# OBDShield_1_1.net
KiCad netlist of a schematic drawn in EAGLE
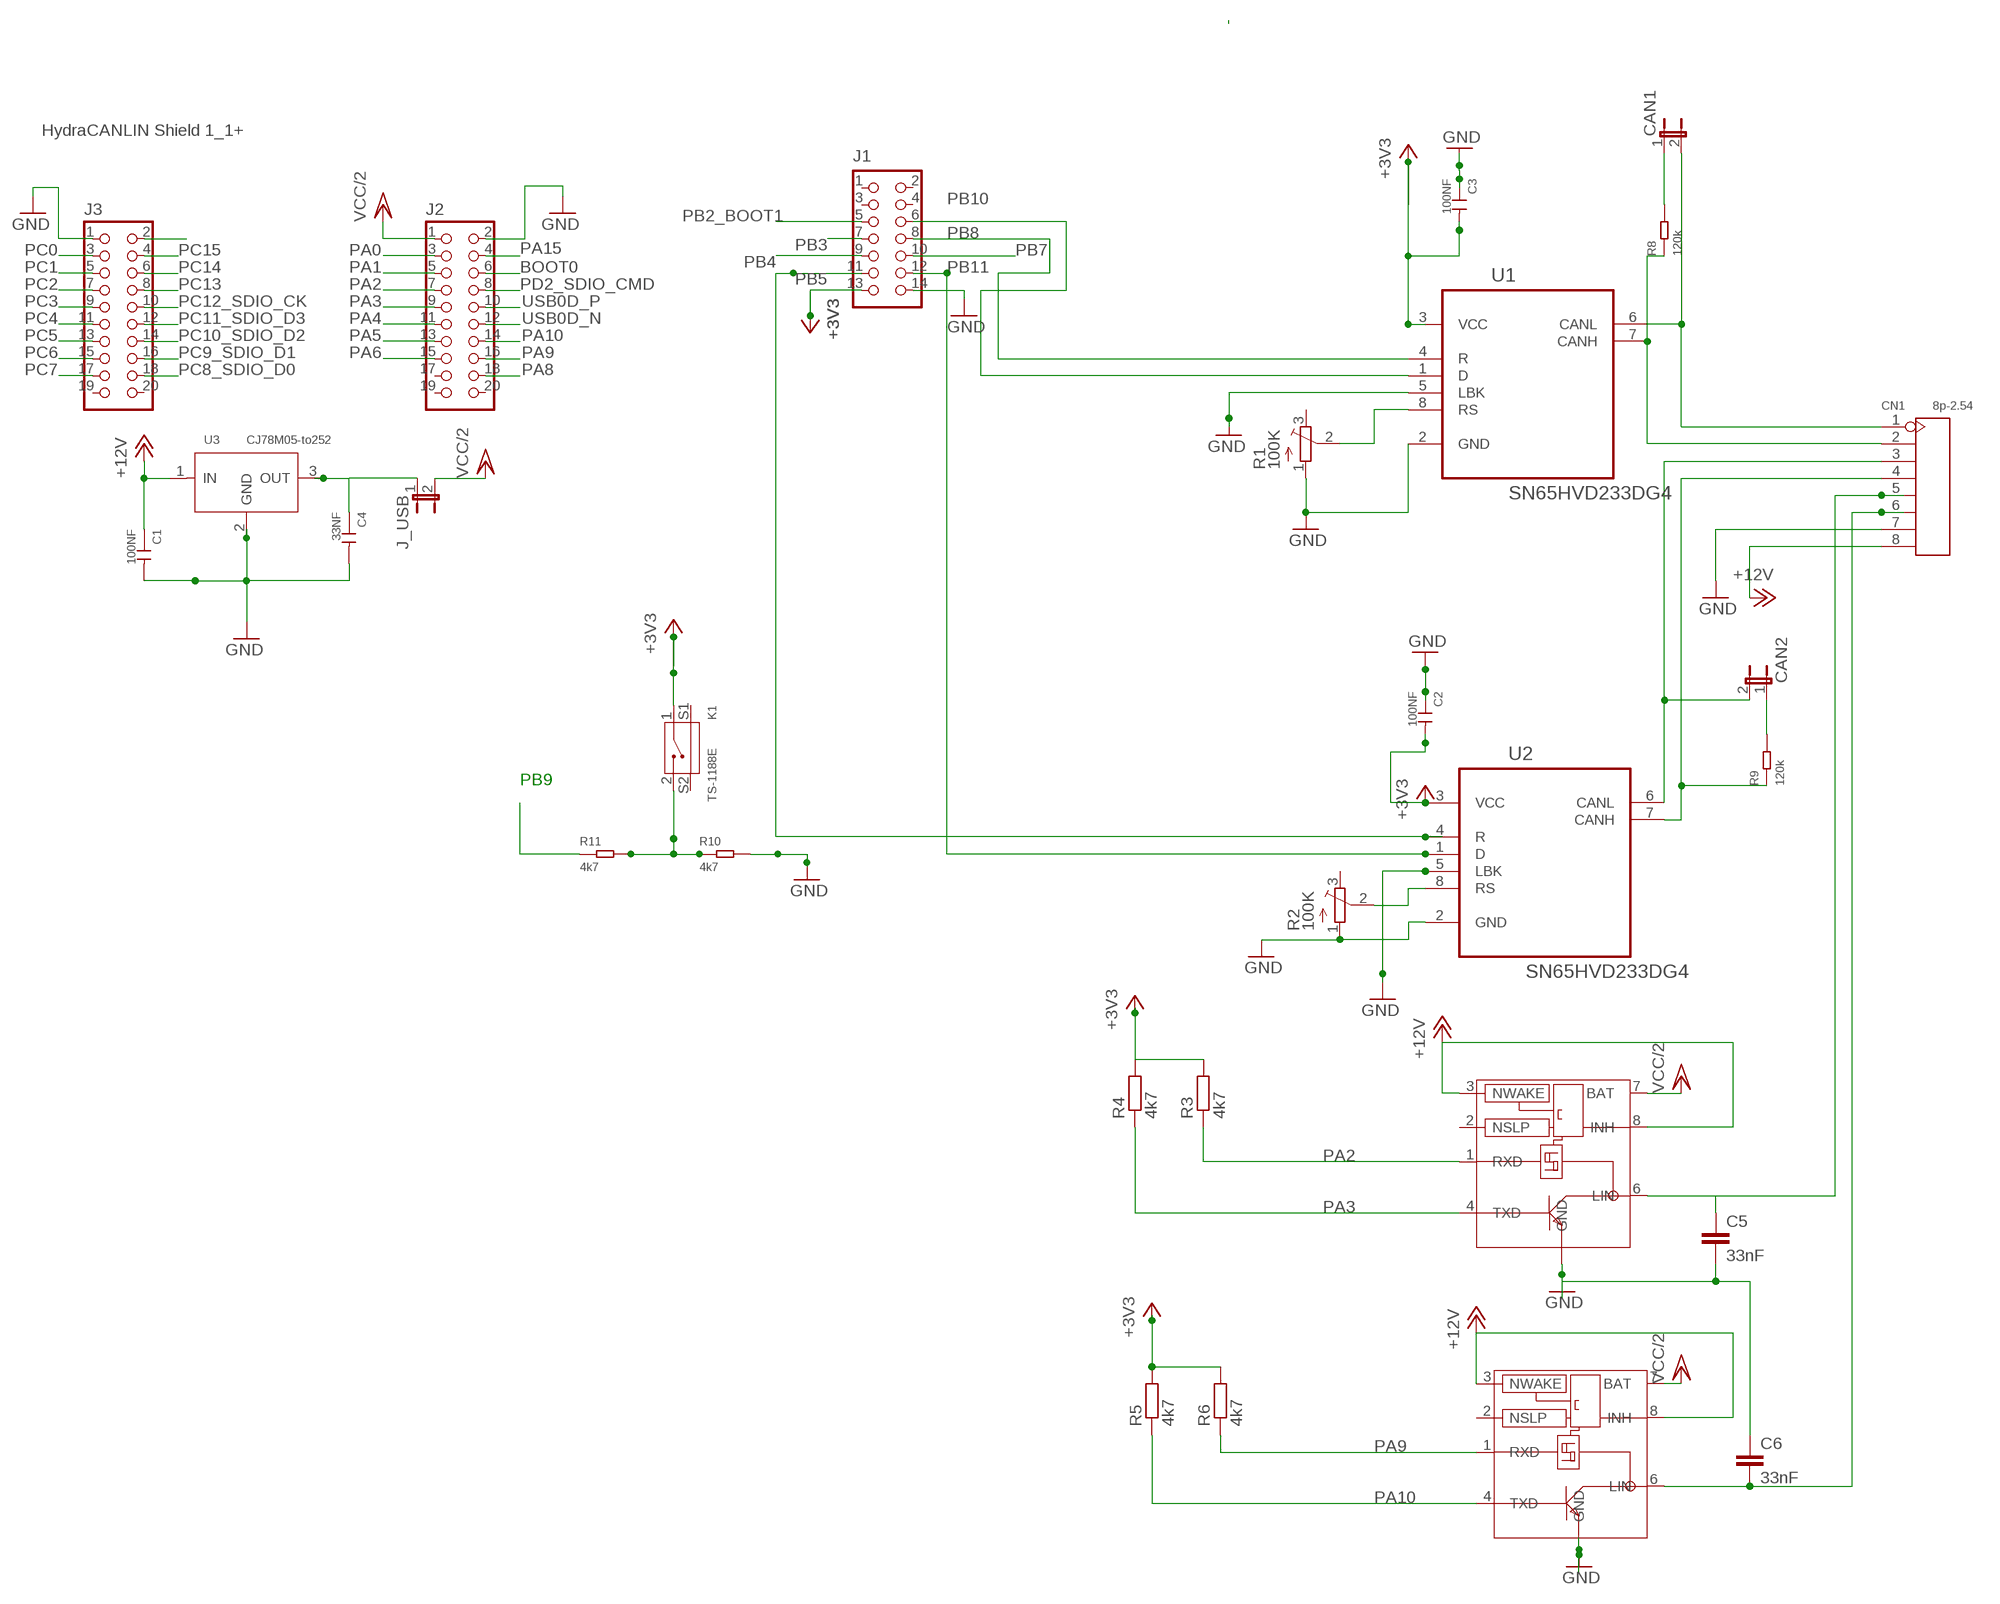
[diagram p0: schematic, sheet 1]

(export (version "E")
  (design (tool "Eeschema 10.0.6"))
  (components
    (comp (ref "C1")
      (value "100NF")
      (footprint "eagle-import:C0805")
      (libsource (lib "eagle-import") (part "CERAMIC-100NF-50V-20%-Y5V(0805)"))
    )
    (comp (ref "C2")
      (value "100NF")
      (footprint "eagle-import:C0805")
      (libsource (lib "eagle-import") (part "CERAMIC-100NF-50V-20%-Y5V(0805)"))
    )
    (comp (ref "C3")
      (value "100NF")
      (footprint "eagle-import:C0805")
      (libsource (lib "eagle-import") (part "CERAMIC-100NF-50V-20%-Y5V(0805)"))
    )
    (comp (ref "C4")
      (value "33NF")
      (footprint "eagle-import:C0805")
      (libsource (lib "eagle-import") (part "CERAMIC-100NF-50V-20%-Y5V(0805)"))
    )
    (comp (ref "C5")
      (value "33nF")
      (footprint "eagle-import:1206")
      (libsource (lib "eagle-import") (part "CAP1206"))
    )
    (comp (ref "C6")
      (value "33nF")
      (footprint "eagle-import:1206")
      (libsource (lib "eagle-import") (part "CAP1206"))
    )
    (comp (ref "CAN1")
      (value "JP1E")
      (footprint "eagle-import:JP1")
      (libsource (lib "eagle-import") (part "JP1E"))
    )
    (comp (ref "CAN2")
      (value "JP1E")
      (footprint "eagle-import:JP1")
      (libsource (lib "eagle-import") (part "JP1E"))
    )
    (comp (ref "CN1")
      (value "8p-2.54")
      (footprint "eagle-import:H8-2.54")
      (fields (field (name "MPN") "F185-1108A1BSYC1"))
      (libsource (lib "eagle-import") (part "DIP-BLACK-FEMALE-HEADER-VERT(8P-2.54)"))
    )
    (comp (ref "J1")
      (value "HYDRABUS_SHIELD_CON_HEADER_2X07")
      (footprint "eagle-import:HYDRABUS_SHIELD_M2X7")
      (libsource (lib "eagle-import") (part "HYDRABUS_SHIELD_CON_HEADER_2X07"))
    )
    (comp (ref "J2")
      (value "HYDRABUS_SHIELD_CON_HEADER_2X10")
      (footprint "eagle-import:HYDRABUS_SHIELD_M2X10")
      (libsource (lib "eagle-import") (part "HYDRABUS_SHIELD_CON_HEADER_2X10"))
    )
    (comp (ref "J3")
      (value "HYDRABUS_SHIELD_CON_HEADER_2X10")
      (footprint "eagle-import:HYDRABUS_SHIELD_M2X10")
      (libsource (lib "eagle-import") (part "HYDRABUS_SHIELD_CON_HEADER_2X10"))
    )
    (comp (ref "J_USB")
      (value "JP1E")
      (footprint "eagle-import:JP1")
      (libsource (lib "eagle-import") (part "JP1E"))
    )
    (comp (ref "K1")
      (value "TS-1188E")
      (footprint "eagle-import:SW4-SMD-7.0X3.5X3.5MM-90D")
      (libsource (lib "eagle-import") (part "SMD-BUTTON-2+2P"))
    )
    (comp (ref "LIN1")
      (value "TJA1020SO8")
      (footprint "eagle-import:SO8")
      (libsource (lib "eagle-import") (part "TJA1020SO8"))
    )
    (comp (ref "LIN2")
      (value "TJA1020SO8")
      (footprint "eagle-import:SO8")
      (libsource (lib "eagle-import") (part "TJA1020SO8"))
    )
    (comp (ref "R1")
      (value "100K")
      (footprint "eagle-import:SM-42_43A")
      (libsource (lib "eagle-import") (part "TRIM_EU-SM-42/43A"))
    )
    (comp (ref "R2")
      (value "100K")
      (footprint "eagle-import:SM-42_43A")
      (libsource (lib "eagle-import") (part "TRIM_EU-SM-42/43A"))
    )
    (comp (ref "R3")
      (value "4k7")
      (footprint "eagle-import:M1206")
      (libsource (lib "eagle-import") (part "R-EU_M1206"))
    )
    (comp (ref "R4")
      (value "4k7")
      (footprint "eagle-import:M1206")
      (libsource (lib "eagle-import") (part "R-EU_M1206"))
    )
    (comp (ref "R5")
      (value "4k7")
      (footprint "eagle-import:M1206")
      (libsource (lib "eagle-import") (part "R-EU_M1206"))
    )
    (comp (ref "R6")
      (value "4k7")
      (footprint "eagle-import:M1206")
      (libsource (lib "eagle-import") (part "R-EU_M1206"))
    )
    (comp (ref "R8")
      (value "120k")
      (footprint "eagle-import:R1206")
      (fields (field (name "MPN") "RC1206FR-0733KL"))
      (libsource (lib "eagle-import") (part "SMD-RES-33K-1%-1/4W(1206)"))
    )
    (comp (ref "R9")
      (value "120k")
      (footprint "eagle-import:R1206")
      (fields (field (name "MPN") "RC1206FR-0733KL"))
      (libsource (lib "eagle-import") (part "SMD-RES-33K-1%-1/4W(1206)"))
    )
    (comp (ref "R10")
      (value "4k7")
      (footprint "eagle-import:R1206")
      (fields (field (name "MPN") "RC1206FR-0733KL"))
      (libsource (lib "eagle-import") (part "SMD-RES-33K-1%-1/4W(1206)"))
    )
    (comp (ref "R11")
      (value "4k7")
      (footprint "eagle-import:R1206")
      (fields (field (name "MPN") "RC1206FR-0733KL"))
      (libsource (lib "eagle-import") (part "SMD-RES-33K-1%-1/4W(1206)"))
    )
    (comp (ref "U1")
      (value "SN65HVD233DG4")
      (footprint "eagle-import:SOIC127P600X175-8N")
      (libsource (lib "eagle-import") (part "SN65HVD233DG4"))
    )
    (comp (ref "U2")
      (value "SN65HVD233DG4")
      (footprint "eagle-import:SOIC127P600X175-8N")
      (libsource (lib "eagle-import") (part "SN65HVD233DG4"))
    )
    (comp (ref "U3")
      (value "CJ78M05-to252")
      (footprint "eagle-import:TO-252")
      (fields (field (name "MPN") "CJ78M05"))
      (libsource (lib "eagle-import") (part "PMIC-CJ78M05(TO-252)"))
    )
  )
  (nets
    (net (code "1") (name "+3V3") (class "Default")
      (node (ref "C2") (pin "2") (pinfunction "2_2") (pintype "passive"))
      (node (ref "C3") (pin "2") (pinfunction "2_2") (pintype "passive"))
      (node (ref "J1") (pin "13") (pinfunction "13_13") (pintype "passive"))
      (node (ref "K1") (pin "1") (pinfunction "1_1") (pintype "bidirectional"))
      (node (ref "R3") (pin "2") (pinfunction "2_2") (pintype "passive"))
      (node (ref "R4") (pin "2") (pinfunction "2_2") (pintype "passive"))
      (node (ref "R5") (pin "2") (pinfunction "2_2") (pintype "passive"))
      (node (ref "R6") (pin "2") (pinfunction "2_2") (pintype "passive"))
      (node (ref "U1") (pin "3") (pinfunction "VCC_3") (pintype "power_in"))
      (node (ref "U2") (pin "3") (pinfunction "VCC_3") (pintype "power_in"))
    )
    (net (code "2") (name "+12V") (class "Default")
      (node (ref "C1") (pin "1") (pinfunction "1_1") (pintype "passive"))
      (node (ref "CN1") (pin "8") (pinfunction "8_8") (pintype "bidirectional"))
      (node (ref "LIN1") (pin "3") (pinfunction "NWAKE_3") (pintype "input"))
      (node (ref "LIN1") (pin "8") (pinfunction "INH_8") (pintype "output"))
      (node (ref "LIN2") (pin "3") (pinfunction "NWAKE_3") (pintype "input"))
      (node (ref "LIN2") (pin "8") (pinfunction "INH_8") (pintype "output"))
      (node (ref "U3") (pin "1") (pinfunction "IN_1") (pintype "bidirectional"))
    )
    (net (code "3") (name "/BOOT0") (class "Default")
      (node (ref "J2") (pin "6") (pinfunction "6_6") (pintype "passive"))
    )
    (net (code "4") (name "/PA0") (class "Default")
      (node (ref "J2") (pin "3") (pinfunction "3_3") (pintype "passive"))
    )
    (net (code "5") (name "/PA1") (class "Default")
      (node (ref "J2") (pin "5") (pinfunction "5_5") (pintype "passive"))
    )
    (net (code "6") (name "/PA2") (class "Default")
      (node (ref "J2") (pin "7") (pinfunction "7_7") (pintype "passive"))
      (node (ref "LIN2") (pin "1") (pinfunction "RXD_1") (pintype "input"))
      (node (ref "R3") (pin "1") (pinfunction "1_1") (pintype "passive"))
    )
    (net (code "7") (name "/PA3") (class "Default")
      (node (ref "J2") (pin "9") (pinfunction "9_9") (pintype "passive"))
      (node (ref "LIN2") (pin "4") (pinfunction "TXD_4") (pintype "output"))
      (node (ref "R4") (pin "1") (pinfunction "1_1") (pintype "passive"))
    )
    (net (code "8") (name "/PA4") (class "Default")
      (node (ref "J2") (pin "11") (pinfunction "11_11") (pintype "passive"))
    )
    (net (code "9") (name "/PA5") (class "Default")
      (node (ref "J2") (pin "13") (pinfunction "13_13") (pintype "passive"))
    )
    (net (code "10") (name "/PA6") (class "Default")
      (node (ref "J2") (pin "15") (pinfunction "15_15") (pintype "passive"))
    )
    (net (code "11") (name "/PA8") (class "Default")
      (node (ref "J2") (pin "18") (pinfunction "18_18") (pintype "passive"))
    )
    (net (code "12") (name "/PA9") (class "Default")
      (node (ref "J2") (pin "16") (pinfunction "16_16") (pintype "passive"))
      (node (ref "LIN1") (pin "1") (pinfunction "RXD_1") (pintype "input"))
      (node (ref "R6") (pin "1") (pinfunction "1_1") (pintype "passive"))
    )
    (net (code "13") (name "/PA10") (class "Default")
      (node (ref "J2") (pin "14") (pinfunction "14_14") (pintype "passive"))
      (node (ref "LIN1") (pin "4") (pinfunction "TXD_4") (pintype "output"))
      (node (ref "R5") (pin "1") (pinfunction "1_1") (pintype "passive"))
    )
    (net (code "14") (name "/PA15") (class "Default")
      (node (ref "J2") (pin "4") (pinfunction "4_4") (pintype "passive"))
    )
    (net (code "15") (name "/PB2_BOOT1") (class "Default")
      (node (ref "J1") (pin "5") (pinfunction "5_5") (pintype "passive"))
    )
    (net (code "16") (name "/PB3") (class "Default")
      (node (ref "J1") (pin "7") (pinfunction "7_7") (pintype "passive"))
    )
    (net (code "17") (name "/PB4") (class "Default")
      (node (ref "J1") (pin "9") (pinfunction "9_9") (pintype "passive"))
    )
    (net (code "18") (name "/PB5") (class "Default")
      (node (ref "J1") (pin "11") (pinfunction "11_11") (pintype "passive"))
      (node (ref "U2") (pin "4") (pinfunction "R_4") (pintype "input"))
    )
    (net (code "19") (name "/PB7") (class "Default")
      (node (ref "J1") (pin "10") (pinfunction "10_10") (pintype "passive"))
      (node (ref "R11") (pin "1") (pinfunction "1_1") (pintype "passive"))
    )
    (net (code "20") (name "/PB8") (class "Default")
      (node (ref "J1") (pin "8") (pinfunction "8_8") (pintype "passive"))
      (node (ref "U1") (pin "4") (pinfunction "R_4") (pintype "input"))
    )
    (net (code "21") (name "/PB10") (class "Default")
      (node (ref "J1") (pin "6") (pinfunction "6_6") (pintype "passive"))
      (node (ref "U1") (pin "1") (pinfunction "D_1") (pintype "input"))
    )
    (net (code "22") (name "/PB11") (class "Default")
      (node (ref "J1") (pin "12") (pinfunction "12_12") (pintype "passive"))
      (node (ref "U2") (pin "1") (pinfunction "D_1") (pintype "input"))
    )
    (net (code "23") (name "/PC0") (class "Default")
      (node (ref "J3") (pin "3") (pinfunction "3_3") (pintype "passive"))
    )
    (net (code "24") (name "/PC1") (class "Default")
      (node (ref "J3") (pin "5") (pinfunction "5_5") (pintype "passive"))
    )
    (net (code "25") (name "/PC2") (class "Default")
      (node (ref "J3") (pin "7") (pinfunction "7_7") (pintype "passive"))
    )
    (net (code "26") (name "/PC3") (class "Default")
      (node (ref "J3") (pin "9") (pinfunction "9_9") (pintype "passive"))
    )
    (net (code "27") (name "/PC4") (class "Default")
      (node (ref "J3") (pin "11") (pinfunction "11_11") (pintype "passive"))
    )
    (net (code "28") (name "/PC5") (class "Default")
      (node (ref "J3") (pin "13") (pinfunction "13_13") (pintype "passive"))
    )
    (net (code "29") (name "/PC6") (class "Default")
      (node (ref "J3") (pin "15") (pinfunction "15_15") (pintype "passive"))
    )
    (net (code "30") (name "/PC7") (class "Default")
      (node (ref "J3") (pin "17") (pinfunction "17_17") (pintype "passive"))
    )
    (net (code "31") (name "/PC8_SDIO_D0") (class "Default")
      (node (ref "J3") (pin "18") (pinfunction "18_18") (pintype "passive"))
    )
    (net (code "32") (name "/PC9_SDIO_D1") (class "Default")
      (node (ref "J3") (pin "16") (pinfunction "16_16") (pintype "passive"))
    )
    (net (code "33") (name "/PC10_SDIO_D2") (class "Default")
      (node (ref "J3") (pin "14") (pinfunction "14_14") (pintype "passive"))
    )
    (net (code "34") (name "/PC11_SDIO_D3") (class "Default")
      (node (ref "J3") (pin "12") (pinfunction "12_12") (pintype "passive"))
    )
    (net (code "35") (name "/PC12_SDIO_CK") (class "Default")
      (node (ref "J3") (pin "10") (pinfunction "10_10") (pintype "passive"))
    )
    (net (code "36") (name "/PC13") (class "Default")
      (node (ref "J3") (pin "8") (pinfunction "8_8") (pintype "passive"))
    )
    (net (code "37") (name "/PC14") (class "Default")
      (node (ref "J3") (pin "6") (pinfunction "6_6") (pintype "passive"))
    )
    (net (code "38") (name "/PC15") (class "Default")
      (node (ref "J3") (pin "4") (pinfunction "4_4") (pintype "passive"))
    )
    (net (code "39") (name "/PD2_SDIO_CMD") (class "Default")
      (node (ref "J2") (pin "8") (pinfunction "8_8") (pintype "passive"))
    )
    (net (code "40") (name "/USB0D_N") (class "Default")
      (node (ref "J2") (pin "12") (pinfunction "12_12") (pintype "passive"))
    )
    (net (code "41") (name "/USB0D_P") (class "Default")
      (node (ref "J2") (pin "10") (pinfunction "10_10") (pintype "passive"))
    )
    (net (code "42") (name "GND") (class "Default")
      (node (ref "C1") (pin "2") (pinfunction "2_2") (pintype "passive"))
      (node (ref "C2") (pin "1") (pinfunction "1_1") (pintype "passive"))
      (node (ref "C3") (pin "1") (pinfunction "1_1") (pintype "passive"))
      (node (ref "C4") (pin "2") (pinfunction "2_2") (pintype "passive"))
      (node (ref "C5") (pin "2") (pinfunction "2_2") (pintype "passive"))
      (node (ref "C6") (pin "1") (pinfunction "1_1") (pintype "passive"))
      (node (ref "CN1") (pin "7") (pinfunction "7_7") (pintype "bidirectional"))
      (node (ref "J1") (pin "14") (pinfunction "14_14") (pintype "passive"))
      (node (ref "J2") (pin "2") (pinfunction "2_2") (pintype "passive"))
      (node (ref "J3") (pin "1") (pinfunction "1_1") (pintype "passive"))
      (node (ref "LIN1") (pin "5") (pinfunction "GND_5") (pintype "power_in"))
      (node (ref "LIN2") (pin "5") (pinfunction "GND_5") (pintype "power_in"))
      (node (ref "R1") (pin "1") (pinfunction "A_1") (pintype "passive"))
      (node (ref "R10") (pin "2") (pinfunction "2_2") (pintype "passive"))
      (node (ref "R2") (pin "1") (pinfunction "A_1") (pintype "passive"))
      (node (ref "U1") (pin "2") (pinfunction "GND_2") (pintype "passive"))
      (node (ref "U1") (pin "5") (pinfunction "LBK_5") (pintype "passive"))
      (node (ref "U2") (pin "2") (pinfunction "GND_2") (pintype "passive"))
      (node (ref "U2") (pin "5") (pinfunction "LBK_5") (pintype "passive"))
      (node (ref "U3") (pin "2") (pinfunction "GND_2") (pintype "bidirectional"))
    )
    (net (code "43") (name "Net-(CAN1-Pad1)") (class "Default")
      (node (ref "CAN1") (pin "1") (pinfunction "1_1") (pintype "passive"))
      (node (ref "R8") (pin "2") (pinfunction "2_2") (pintype "passive"))
    )
    (net (code "44") (name "Net-(CAN2-Pad1)") (class "Default")
      (node (ref "CAN2") (pin "1") (pinfunction "1_1") (pintype "passive"))
      (node (ref "R9") (pin "2") (pinfunction "2_2") (pintype "passive"))
    )
    (net (code "45") (name "Net-(K1-Pad2)") (class "Default")
      (node (ref "K1") (pin "2") (pinfunction "2_2") (pintype "bidirectional"))
      (node (ref "R10") (pin "1") (pinfunction "1_1") (pintype "passive"))
      (node (ref "R11") (pin "2") (pinfunction "2_2") (pintype "passive"))
    )
    (net (code "46") (name "Net-(LIN1-LIN)") (class "Default")
      (node (ref "C6") (pin "2") (pinfunction "2_2") (pintype "passive"))
      (node (ref "CN1") (pin "6") (pinfunction "6_6") (pintype "bidirectional"))
      (node (ref "LIN1") (pin "6") (pinfunction "LIN_6") (pintype "bidirectional"))
    )
    (net (code "47") (name "Net-(LIN2-LIN)") (class "Default")
      (node (ref "C5") (pin "1") (pinfunction "1_1") (pintype "passive"))
      (node (ref "CN1") (pin "5") (pinfunction "5_5") (pintype "bidirectional"))
      (node (ref "LIN2") (pin "6") (pinfunction "LIN_6") (pintype "bidirectional"))
    )
    (net (code "48") (name "Net-(R1-S)") (class "Default")
      (node (ref "R1") (pin "2") (pinfunction "S_2") (pintype "passive"))
      (node (ref "U1") (pin "8") (pinfunction "RS_8") (pintype "input"))
    )
    (net (code "49") (name "Net-(R2-S)") (class "Default")
      (node (ref "R2") (pin "2") (pinfunction "S_2") (pintype "passive"))
      (node (ref "U2") (pin "8") (pinfunction "RS_8") (pintype "input"))
    )
    (net (code "50") (name "Net-(U1-CANH)") (class "Default")
      (node (ref "CN1") (pin "2") (pinfunction "2_2") (pintype "bidirectional"))
      (node (ref "R8") (pin "1") (pinfunction "1_1") (pintype "passive"))
      (node (ref "U1") (pin "7") (pinfunction "CANH_7") (pintype "output"))
    )
    (net (code "51") (name "Net-(U1-CANL)") (class "Default")
      (node (ref "CAN1") (pin "2") (pinfunction "2_2") (pintype "passive"))
      (node (ref "CN1") (pin "1") (pinfunction "1_1") (pintype "bidirectional"))
      (node (ref "U1") (pin "6") (pinfunction "CANL_6") (pintype "output"))
    )
    (net (code "52") (name "Net-(U2-CANH)") (class "Default")
      (node (ref "CN1") (pin "4") (pinfunction "4_4") (pintype "bidirectional"))
      (node (ref "R9") (pin "1") (pinfunction "1_1") (pintype "passive"))
      (node (ref "U2") (pin "7") (pinfunction "CANH_7") (pintype "output"))
    )
    (net (code "53") (name "Net-(U2-CANL)") (class "Default")
      (node (ref "CAN2") (pin "2") (pinfunction "2_2") (pintype "passive"))
      (node (ref "CN1") (pin "3") (pinfunction "3_3") (pintype "bidirectional"))
      (node (ref "U2") (pin "6") (pinfunction "CANL_6") (pintype "output"))
    )
    (net (code "54") (name "Net-(U3-OUT)") (class "Default")
      (node (ref "C4") (pin "1") (pinfunction "1_1") (pintype "passive"))
      (node (ref "J_USB") (pin "1") (pinfunction "1_1") (pintype "passive"))
      (node (ref "U3") (pin "3") (pinfunction "OUT_3") (pintype "bidirectional"))
    )
    (net (code "55") (name "VCC{slash}2") (class "Default")
      (node (ref "J2") (pin "1") (pinfunction "1_1") (pintype "passive"))
      (node (ref "J_USB") (pin "2") (pinfunction "2_2") (pintype "passive"))
      (node (ref "LIN1") (pin "7") (pinfunction "BAT_7") (pintype "power_in"))
      (node (ref "LIN2") (pin "7") (pinfunction "BAT_7") (pintype "power_in"))
    )
    (net (code "56") (name "unconnected-(J1-Pad1)") (class "Default")
      (node (ref "J1") (pin "1") (pinfunction "1_1") (pintype "passive"))
    )
    (net (code "57") (name "unconnected-(J1-Pad2)") (class "Default")
      (node (ref "J1") (pin "2") (pinfunction "2_2") (pintype "passive"))
    )
    (net (code "58") (name "unconnected-(J1-Pad3)") (class "Default")
      (node (ref "J1") (pin "3") (pinfunction "3_3") (pintype "passive"))
    )
    (net (code "59") (name "unconnected-(J1-Pad4)") (class "Default")
      (node (ref "J1") (pin "4") (pinfunction "4_4") (pintype "passive"))
    )
    (net (code "60") (name "unconnected-(J2-Pad17)") (class "Default")
      (node (ref "J2") (pin "17") (pinfunction "17_17") (pintype "passive"))
    )
    (net (code "61") (name "unconnected-(J2-Pad19)") (class "Default")
      (node (ref "J2") (pin "19") (pinfunction "19_19") (pintype "passive"))
    )
    (net (code "62") (name "unconnected-(J2-Pad20)") (class "Default")
      (node (ref "J2") (pin "20") (pinfunction "20_20") (pintype "passive"))
    )
    (net (code "63") (name "unconnected-(J3-Pad2)") (class "Default")
      (node (ref "J3") (pin "2") (pinfunction "2_2") (pintype "passive"))
    )
    (net (code "64") (name "unconnected-(J3-Pad19)") (class "Default")
      (node (ref "J3") (pin "19") (pinfunction "19_19") (pintype "passive"))
    )
    (net (code "65") (name "unconnected-(J3-Pad20)") (class "Default")
      (node (ref "J3") (pin "20") (pinfunction "20_20") (pintype "passive"))
    )
    (net (code "66") (name "unconnected-(K1-PadS1)") (class "Default")
      (node (ref "K1") (pin "S1") (pinfunction "S1_S1") (pintype "bidirectional"))
    )
    (net (code "67") (name "unconnected-(K1-PadS2)") (class "Default")
      (node (ref "K1") (pin "S2") (pinfunction "S2_S2") (pintype "bidirectional"))
    )
    (net (code "68") (name "unconnected-(LIN1-NSLP-Pad2)") (class "Default")
      (node (ref "LIN1") (pin "2") (pinfunction "NSLP_2") (pintype "input"))
    )
    (net (code "69") (name "unconnected-(LIN2-NSLP-Pad2)") (class "Default")
      (node (ref "LIN2") (pin "2") (pinfunction "NSLP_2") (pintype "input"))
    )
    (net (code "70") (name "unconnected-(R1-E-Pad3)") (class "Default")
      (node (ref "R1") (pin "3") (pinfunction "E_3") (pintype "passive"))
    )
    (net (code "71") (name "unconnected-(R2-E-Pad3)") (class "Default")
      (node (ref "R2") (pin "3") (pinfunction "E_3") (pintype "passive"))
    )
  )
)
